# GSM.net
KiCad netlist of a schematic drawn in Altium Designer
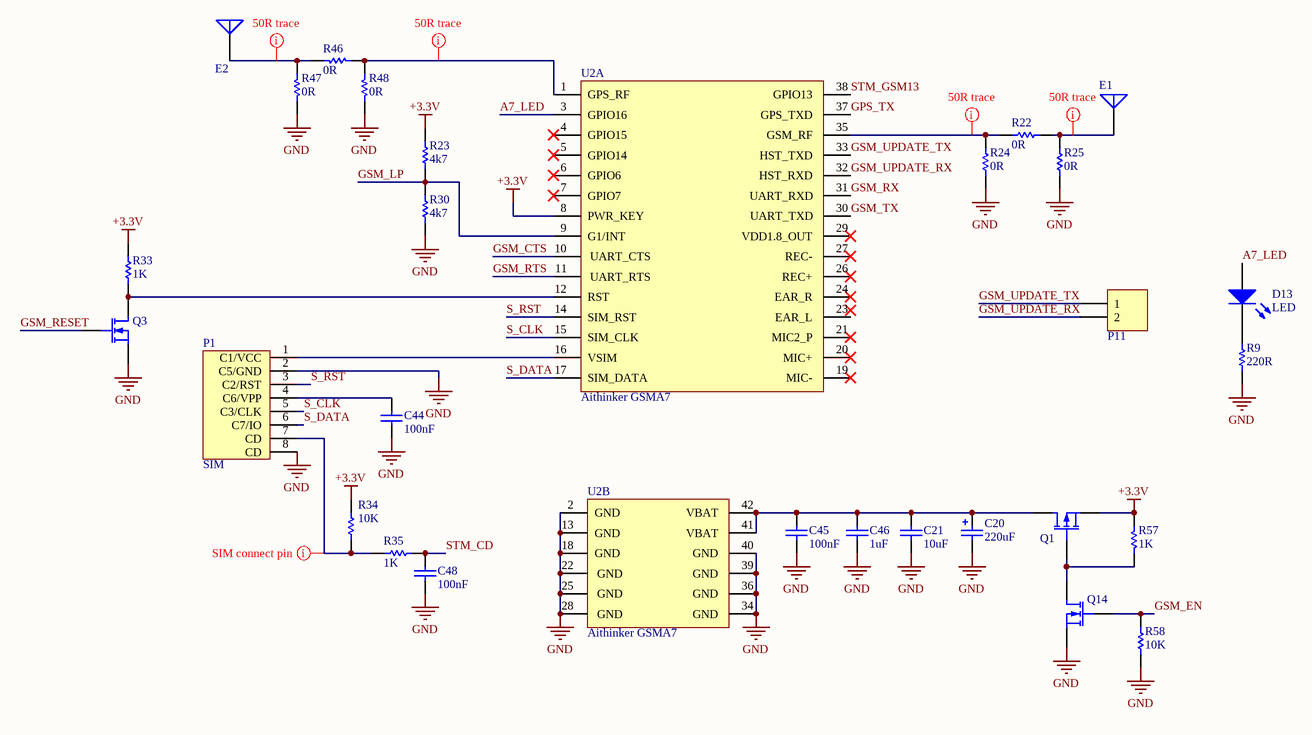
[diagram p0: GSM.SchDoc]

(export (version "E")
  (design (tool "Eeschema 10.0.6"))
  (components
    (comp (ref "C20")
      (value "220uF")
      (footprint "CAP-D")
      (description "Polarized Tantalum Capacitor")
      (fields (field (name "Comment") "Tantalum 220uF"))
      (libsource (lib "integratedLib") (part "Tantalum 220uF"))
    )
    (comp (ref "C21")
      (value "10uF")
      (footprint "C0603")
      (description "Capacitor")
      (fields (field (name "Comment") "Cap 10uF"))
      (libsource (lib "integratedLib") (part "Cap 10uF"))
    )
    (comp (ref "C44")
      (value "100nF")
      (footprint "C0402")
      (description "Capacitor")
      (fields (field (name "Comment") "Cap 100nF"))
      (libsource (lib "integratedLib") (part "Cap 100nF"))
    )
    (comp (ref "C45")
      (value "100nF")
      (footprint "C0402")
      (description "Capacitor")
      (fields (field (name "Comment") "Cap 100nF"))
      (libsource (lib "integratedLib") (part "Cap 100nF"))
    )
    (comp (ref "C46")
      (value "1uF")
      (footprint "C0402")
      (description "Capacitor")
      (fields (field (name "Comment") "Cap 1uF"))
      (libsource (lib "integratedLib") (part "Cap 1uF"))
    )
    (comp (ref "C48")
      (value "100nF")
      (footprint "C0402")
      (description "Capacitor")
      (fields (field (name "Comment") "Cap 100nF"))
      (libsource (lib "integratedLib") (part "Cap 100nF"))
    )
    (comp (ref "D13")
      (value "LED")
      (footprint "0603LedRed")
      (description "Typical RED GaAs LED")
      (fields (field (name "PUBLISHER") "Altium Limited"))
      (libsource (lib "integratedLib") (part "LED"))
    )
    (comp (ref "E1")
      (value "Antenna")
      (footprint "SMA connector")
      (description "Generic Antenna")
      (fields (field (name "PUBLISHER") "Altium Limited"))
      (libsource (lib "integratedLib") (part "Antenna"))
    )
    (comp (ref "E2")
      (value "Antenna")
      (footprint "SMA connector")
      (description "Generic Antenna")
      (fields (field (name "PUBLISHER") "Altium Limited"))
      (libsource (lib "integratedLib") (part "Antenna"))
    )
    (comp (ref "P1")
      (value "SIM")
      (footprint "SIM TRAY")
      (description "SIM card connector")
      (libsource (lib "integratedLib") (part "SIM"))
    )
    (comp (ref "P11")
      (value "Header 2")
      (footprint "HDR1X2")
      (description "Header, 2-Pin")
      (fields (field (name "PUBLISHER") "Altium Limited"))
      (libsource (lib "integratedLib") (part "Header 2"))
    )
    (comp (ref "Q1")
      (value "AO3401A")
      (footprint "SOT23")
      (description "P-Channel MOSFET AO3401A")
      (fields (field (name "PUBLISHER") "Altium Limited"))
      (libsource (lib "integratedLib") (part "MOSFET-P"))
    )
    (comp (ref "Q3")
      (value "AO3400A")
      (footprint "SOT23")
      (description "N-MOSFET AO3400A")
      (fields (field (name "PUBLISHER") "Altium Limited"))
      (libsource (lib "integratedLib") (part "MOSFET-N"))
    )
    (comp (ref "Q14")
      (value "AO3400A")
      (footprint "SOT23")
      (description "N-MOSFET AO3400A")
      (fields (field (name "PUBLISHER") "Altium Limited"))
      (libsource (lib "integratedLib") (part "MOSFET-N"))
    )
    (comp (ref "R9")
      (value "220R")
      (footprint "R0402")
      (description "Resistor")
      (fields (field (name "Comment") "Res_220R"))
      (libsource (lib "integratedLib") (part "Res_220R"))
    )
    (comp (ref "R22")
      (value "0R")
      (footprint "R0402")
      (description "Resistor")
      (fields (field (name "Comment") "Res_0R"))
      (libsource (lib "integratedLib") (part "Res_0R"))
    )
    (comp (ref "R23")
      (value "4k7")
      (footprint "R0402")
      (description "Resistor")
      (fields (field (name "Comment") "Res_4k7"))
      (libsource (lib "integratedLib") (part "Res_4k7"))
    )
    (comp (ref "R24")
      (value "0R")
      (footprint "R0402")
      (description "Resistor")
      (fields (field (name "Comment") "Res_0R"))
      (libsource (lib "integratedLib") (part "Res_0R"))
    )
    (comp (ref "R25")
      (value "0R")
      (footprint "R0402")
      (description "Resistor")
      (fields (field (name "Comment") "Res_0R"))
      (libsource (lib "integratedLib") (part "Res_0R"))
    )
    (comp (ref "R30")
      (value "4k7")
      (footprint "R0402")
      (description "Resistor")
      (fields (field (name "Comment") "Res_4k7"))
      (libsource (lib "integratedLib") (part "Res_4k7"))
    )
    (comp (ref "R33")
      (value "1K")
      (footprint "R0402")
      (description "Resistor")
      (fields (field (name "Comment") "Res_1K"))
      (libsource (lib "integratedLib") (part "Res_1K"))
    )
    (comp (ref "R34")
      (value "10K")
      (footprint "R0402")
      (description "Resistor")
      (fields (field (name "Comment") "Res_10K"))
      (libsource (lib "integratedLib") (part "Res_10K"))
    )
    (comp (ref "R35")
      (value "1K")
      (footprint "R0402")
      (description "Resistor")
      (fields (field (name "Comment") "Res_1K"))
      (libsource (lib "integratedLib") (part "Res_1K"))
    )
    (comp (ref "R46")
      (value "0R")
      (footprint "R0402")
      (description "Resistor")
      (fields (field (name "Comment") "Res_0R"))
      (libsource (lib "integratedLib") (part "Res_0R"))
    )
    (comp (ref "R47")
      (value "0R")
      (footprint "R0402")
      (description "Resistor")
      (fields (field (name "Comment") "Res_0R"))
      (libsource (lib "integratedLib") (part "Res_0R"))
    )
    (comp (ref "R48")
      (value "0R")
      (footprint "R0402")
      (description "Resistor")
      (fields (field (name "Comment") "Res_0R"))
      (libsource (lib "integratedLib") (part "Res_0R"))
    )
    (comp (ref "R57")
      (value "1K")
      (footprint "R0402")
      (description "Resistor")
      (fields (field (name "Comment") "Res_1K"))
      (libsource (lib "integratedLib") (part "Res_1K"))
    )
    (comp (ref "R58")
      (value "10K")
      (footprint "R0402")
      (description "Resistor")
      (fields (field (name "Comment") "Res_10K"))
      (libsource (lib "integratedLib") (part "Res_10K"))
    )
    (comp (ref "U2")
      (value "Aithinker GSMA7")
      (footprint "A7")
      (description "Aitkinker GSM A7 module")
      (fields (field (name "MANUFACTURER") "STMicroelectronics") (field (name "PARTNUMBER") "STM32L152CCU6"))
      (libsource (lib "integratedLib") (part "GSM_A7"))
    )
  )
  (nets
    (net (code "1") (name "+3.3V") (class "Default")
      (node (ref "Q1") (pin "2") (pinfunction "S_2") (pintype "passive"))
      (node (ref "R23") (pin "2") (pinfunction "2_2") (pintype "passive"))
      (node (ref "R33") (pin "2") (pinfunction "2_2") (pintype "passive"))
      (node (ref "R34") (pin "2") (pinfunction "2_2") (pintype "passive"))
      (node (ref "R57") (pin "2") (pinfunction "2_2") (pintype "passive"))
      (node (ref "U2") (pin "8") (pinfunction "PWR_KEY_8") (pintype "power_in"))
    )
    (net (code "2") (name "/A7_LED") (class "Default")
      (node (ref "D13") (pin "1") (pinfunction "A_1") (pintype "passive"))
      (node (ref "U2") (pin "3") (pinfunction "GPIO16_3") (pintype "passive"))
    )
    (net (code "3") (name "/GPS_TX") (class "Default")
      (node (ref "U2") (pin "37") (pinfunction "GPS_TXD_37") (pintype "passive"))
    )
    (net (code "4") (name "/GSM_CTS") (class "Default")
      (node (ref "U2") (pin "10") (pinfunction "UART_CTS_10") (pintype "passive"))
    )
    (net (code "5") (name "/GSM_EN") (class "Default")
      (node (ref "Q14") (pin "1") (pinfunction "G_1") (pintype "passive"))
      (node (ref "R58") (pin "2") (pinfunction "2_2") (pintype "passive"))
    )
    (net (code "6") (name "/GSM_LP") (class "Default")
      (node (ref "R23") (pin "1") (pinfunction "1_1") (pintype "passive"))
      (node (ref "R30") (pin "2") (pinfunction "2_2") (pintype "passive"))
      (node (ref "U2") (pin "9") (pinfunction "G1/INT_9") (pintype "passive"))
    )
    (net (code "7") (name "/GSM_RESET") (class "Default")
      (node (ref "Q3") (pin "1") (pinfunction "G_1") (pintype "passive"))
    )
    (net (code "8") (name "/GSM_RTS") (class "Default")
      (node (ref "U2") (pin "11") (pinfunction "UART_RTS_11") (pintype "passive"))
    )
    (net (code "9") (name "/GSM_RX") (class "Default")
      (node (ref "U2") (pin "31") (pinfunction "UART_RXD_31") (pintype "passive"))
    )
    (net (code "10") (name "/GSM_TX") (class "Default")
      (node (ref "U2") (pin "30") (pinfunction "UART_TXD_30") (pintype "passive"))
    )
    (net (code "11") (name "/GSM_UPDATE_RX") (class "Default")
      (node (ref "P11") (pin "2") (pinfunction "2_2") (pintype "passive"))
      (node (ref "U2") (pin "32") (pinfunction "HST_RXD_32") (pintype "passive"))
    )
    (net (code "12") (name "/GSM_UPDATE_TX") (class "Default")
      (node (ref "P11") (pin "1") (pinfunction "1_1") (pintype "passive"))
      (node (ref "U2") (pin "33") (pinfunction "HST_TXD_33") (pintype "passive"))
    )
    (net (code "13") (name "/STM_CD") (class "Default")
      (node (ref "C48") (pin "2") (pinfunction "2_2") (pintype "passive"))
      (node (ref "R35") (pin "2") (pinfunction "2_2") (pintype "passive"))
    )
    (net (code "14") (name "/STM_GSM13") (class "Default")
      (node (ref "U2") (pin "38") (pinfunction "GPIO13_38") (pintype "passive"))
    )
    (net (code "15") (name "/S_CLK") (class "Default")
      (node (ref "P1") (pin "5") (pinfunction "C3/CLK_5") (pintype "passive"))
      (node (ref "U2") (pin "15") (pinfunction "SIM_CLK_15") (pintype "passive"))
    )
    (net (code "16") (name "/S_DATA") (class "Default")
      (node (ref "P1") (pin "6") (pinfunction "C7/IO_6") (pintype "passive"))
      (node (ref "U2") (pin "17") (pinfunction "SIM_DATA_17") (pintype "passive"))
    )
    (net (code "17") (name "/S_RST") (class "Default")
      (node (ref "P1") (pin "3") (pinfunction "C2/RST_3") (pintype "passive"))
      (node (ref "U2") (pin "14") (pinfunction "SIM_RST_14") (pintype "passive"))
    )
    (net (code "18") (name "GND") (class "Default")
      (node (ref "C20") (pin "1") (pinfunction "1_1") (pintype "passive"))
      (node (ref "C21") (pin "1") (pinfunction "1_1") (pintype "passive"))
      (node (ref "C44") (pin "1") (pinfunction "1_1") (pintype "passive"))
      (node (ref "C45") (pin "1") (pinfunction "1_1") (pintype "passive"))
      (node (ref "C46") (pin "1") (pinfunction "1_1") (pintype "passive"))
      (node (ref "C48") (pin "1") (pinfunction "1_1") (pintype "passive"))
      (node (ref "P1") (pin "2") (pinfunction "C5/GND_2") (pintype "passive"))
      (node (ref "P1") (pin "8") (pinfunction "CD_8") (pintype "passive"))
      (node (ref "Q14") (pin "2") (pinfunction "S_2") (pintype "passive"))
      (node (ref "Q3") (pin "2") (pinfunction "S_2") (pintype "passive"))
      (node (ref "R24") (pin "1") (pinfunction "1_1") (pintype "passive"))
      (node (ref "R25") (pin "1") (pinfunction "1_1") (pintype "passive"))
      (node (ref "R30") (pin "1") (pinfunction "1_1") (pintype "passive"))
      (node (ref "R47") (pin "1") (pinfunction "1_1") (pintype "passive"))
      (node (ref "R48") (pin "1") (pinfunction "1_1") (pintype "passive"))
      (node (ref "R58") (pin "1") (pinfunction "1_1") (pintype "passive"))
      (node (ref "R9") (pin "1") (pinfunction "1_1") (pintype "passive"))
      (node (ref "U2") (pin "13") (pinfunction "GND_13") (pintype "passive"))
      (node (ref "U2") (pin "18") (pinfunction "GND_18") (pintype "passive"))
      (node (ref "U2") (pin "2") (pinfunction "GND_2") (pintype "passive"))
      (node (ref "U2") (pin "22") (pinfunction "GND_22") (pintype "passive"))
      (node (ref "U2") (pin "25") (pinfunction "GND_25") (pintype "passive"))
      (node (ref "U2") (pin "28") (pinfunction "GND_28") (pintype "passive"))
      (node (ref "U2") (pin "34") (pinfunction "GND_34") (pintype "passive"))
      (node (ref "U2") (pin "36") (pinfunction "GND_36") (pintype "passive"))
      (node (ref "U2") (pin "39") (pinfunction "GND_39") (pintype "passive"))
      (node (ref "U2") (pin "40") (pinfunction "GND_40") (pintype "passive"))
    )
    (net (code "19") (name "Net-(D13-K)") (class "Default")
      (node (ref "D13") (pin "2") (pinfunction "K_2") (pintype "passive"))
      (node (ref "R9") (pin "2") (pinfunction "2_2") (pintype "passive"))
    )
    (net (code "20") (name "Net-(E1-A)") (class "Default")
      (node (ref "E1") (pin "1") (pinfunction "A_1") (pintype "passive"))
      (node (ref "R22") (pin "2") (pinfunction "2_2") (pintype "passive"))
      (node (ref "R25") (pin "2") (pinfunction "2_2") (pintype "passive"))
    )
    (net (code "21") (name "Net-(E2-A)") (class "Default")
      (node (ref "E2") (pin "1") (pinfunction "A_1") (pintype "passive"))
      (node (ref "R46") (pin "2") (pinfunction "2_2") (pintype "passive"))
      (node (ref "R47") (pin "2") (pinfunction "2_2") (pintype "passive"))
    )
    (net (code "22") (name "Net-(P1-C1{slash}VCC)") (class "Default")
      (node (ref "P1") (pin "1") (pinfunction "C1/VCC_1") (pintype "passive"))
      (node (ref "U2") (pin "16") (pinfunction "VSIM_16") (pintype "passive"))
    )
    (net (code "23") (name "Net-(P1-C6{slash}VPP)") (class "Default")
      (node (ref "C44") (pin "2") (pinfunction "2_2") (pintype "passive"))
      (node (ref "P1") (pin "4") (pinfunction "C6/VPP_4") (pintype "passive"))
    )
    (net (code "24") (name "Net-(P1-CD-Pad7)") (class "Default")
      (node (ref "P1") (pin "7") (pinfunction "CD_7") (pintype "passive"))
      (node (ref "R34") (pin "1") (pinfunction "1_1") (pintype "passive"))
      (node (ref "R35") (pin "1") (pinfunction "1_1") (pintype "passive"))
    )
    (net (code "25") (name "Net-(Q1-D)") (class "Default")
      (node (ref "C20") (pin "2") (pinfunction "2_2") (pintype "passive"))
      (node (ref "C21") (pin "2") (pinfunction "2_2") (pintype "passive"))
      (node (ref "C45") (pin "2") (pinfunction "2_2") (pintype "passive"))
      (node (ref "C46") (pin "2") (pinfunction "2_2") (pintype "passive"))
      (node (ref "Q1") (pin "3") (pinfunction "D_3") (pintype "passive"))
      (node (ref "U2") (pin "41") (pinfunction "VBAT_41") (pintype "passive"))
      (node (ref "U2") (pin "42") (pinfunction "VBAT_42") (pintype "passive"))
    )
    (net (code "26") (name "Net-(Q1-G)") (class "Default")
      (node (ref "Q1") (pin "1") (pinfunction "G_1") (pintype "passive"))
      (node (ref "Q14") (pin "3") (pinfunction "D_3") (pintype "passive"))
      (node (ref "R57") (pin "1") (pinfunction "1_1") (pintype "passive"))
    )
    (net (code "27") (name "Net-(Q3-D)") (class "Default")
      (node (ref "Q3") (pin "3") (pinfunction "D_3") (pintype "passive"))
      (node (ref "R33") (pin "1") (pinfunction "1_1") (pintype "passive"))
      (node (ref "U2") (pin "12") (pinfunction "RST_12") (pintype "passive"))
    )
    (net (code "28") (name "Net-(U2A-GPS_RF)") (class "Default")
      (node (ref "R46") (pin "1") (pinfunction "1_1") (pintype "passive"))
      (node (ref "R48") (pin "2") (pinfunction "2_2") (pintype "passive"))
      (node (ref "U2") (pin "1") (pinfunction "GPS_RF_1") (pintype "passive"))
    )
    (net (code "29") (name "Net-(U2A-GSM_RF)") (class "Default")
      (node (ref "R22") (pin "1") (pinfunction "1_1") (pintype "passive"))
      (node (ref "R24") (pin "2") (pinfunction "2_2") (pintype "passive"))
      (node (ref "U2") (pin "35") (pinfunction "GSM_RF_35") (pintype "passive"))
    )
    (net (code "30") (name "unconnected-(U2A-EAR_L-Pad23)") (class "Default")
      (node (ref "U2") (pin "23") (pinfunction "EAR_L_23") (pintype "passive"))
    )
    (net (code "31") (name "unconnected-(U2A-EAR_R-Pad24)") (class "Default")
      (node (ref "U2") (pin "24") (pinfunction "EAR_R_24") (pintype "passive+no_connect"))
    )
    (net (code "32") (name "unconnected-(U2A-GPIO6-Pad6)") (class "Default")
      (node (ref "U2") (pin "6") (pinfunction "GPIO6_6") (pintype "passive+no_connect"))
    )
    (net (code "33") (name "unconnected-(U2A-GPIO7-Pad7)") (class "Default")
      (node (ref "U2") (pin "7") (pinfunction "GPIO7_7") (pintype "passive+no_connect"))
    )
    (net (code "34") (name "unconnected-(U2A-GPIO14-Pad5)") (class "Default")
      (node (ref "U2") (pin "5") (pinfunction "GPIO14_5") (pintype "passive+no_connect"))
    )
    (net (code "35") (name "unconnected-(U2A-GPIO15-Pad4)") (class "Default")
      (node (ref "U2") (pin "4") (pinfunction "GPIO15_4") (pintype "passive+no_connect"))
    )
    (net (code "36") (name "unconnected-(U2A-MIC+-Pad20)") (class "Default")
      (node (ref "U2") (pin "20") (pinfunction "MIC+_20") (pintype "passive+no_connect"))
    )
    (net (code "37") (name "unconnected-(U2A-MIC--Pad19)") (class "Default")
      (node (ref "U2") (pin "19") (pinfunction "MIC-_19") (pintype "passive+no_connect"))
    )
    (net (code "38") (name "unconnected-(U2A-MIC2_P-Pad21)") (class "Default")
      (node (ref "U2") (pin "21") (pinfunction "MIC2_P_21") (pintype "passive+no_connect"))
    )
    (net (code "39") (name "unconnected-(U2A-REC+-Pad26)") (class "Default")
      (node (ref "U2") (pin "26") (pinfunction "REC+_26") (pintype "passive+no_connect"))
    )
    (net (code "40") (name "unconnected-(U2A-REC--Pad27)") (class "Default")
      (node (ref "U2") (pin "27") (pinfunction "REC-_27") (pintype "passive+no_connect"))
    )
    (net (code "41") (name "unconnected-(U2A-VDD1.8_OUT-Pad29)") (class "Default")
      (node (ref "U2") (pin "29") (pinfunction "VDD1.8_OUT_29") (pintype "passive+no_connect"))
    )
  )
)
